# MaryLadder_8bits.net
KiCad netlist of a schematic drawn in Altium Designer
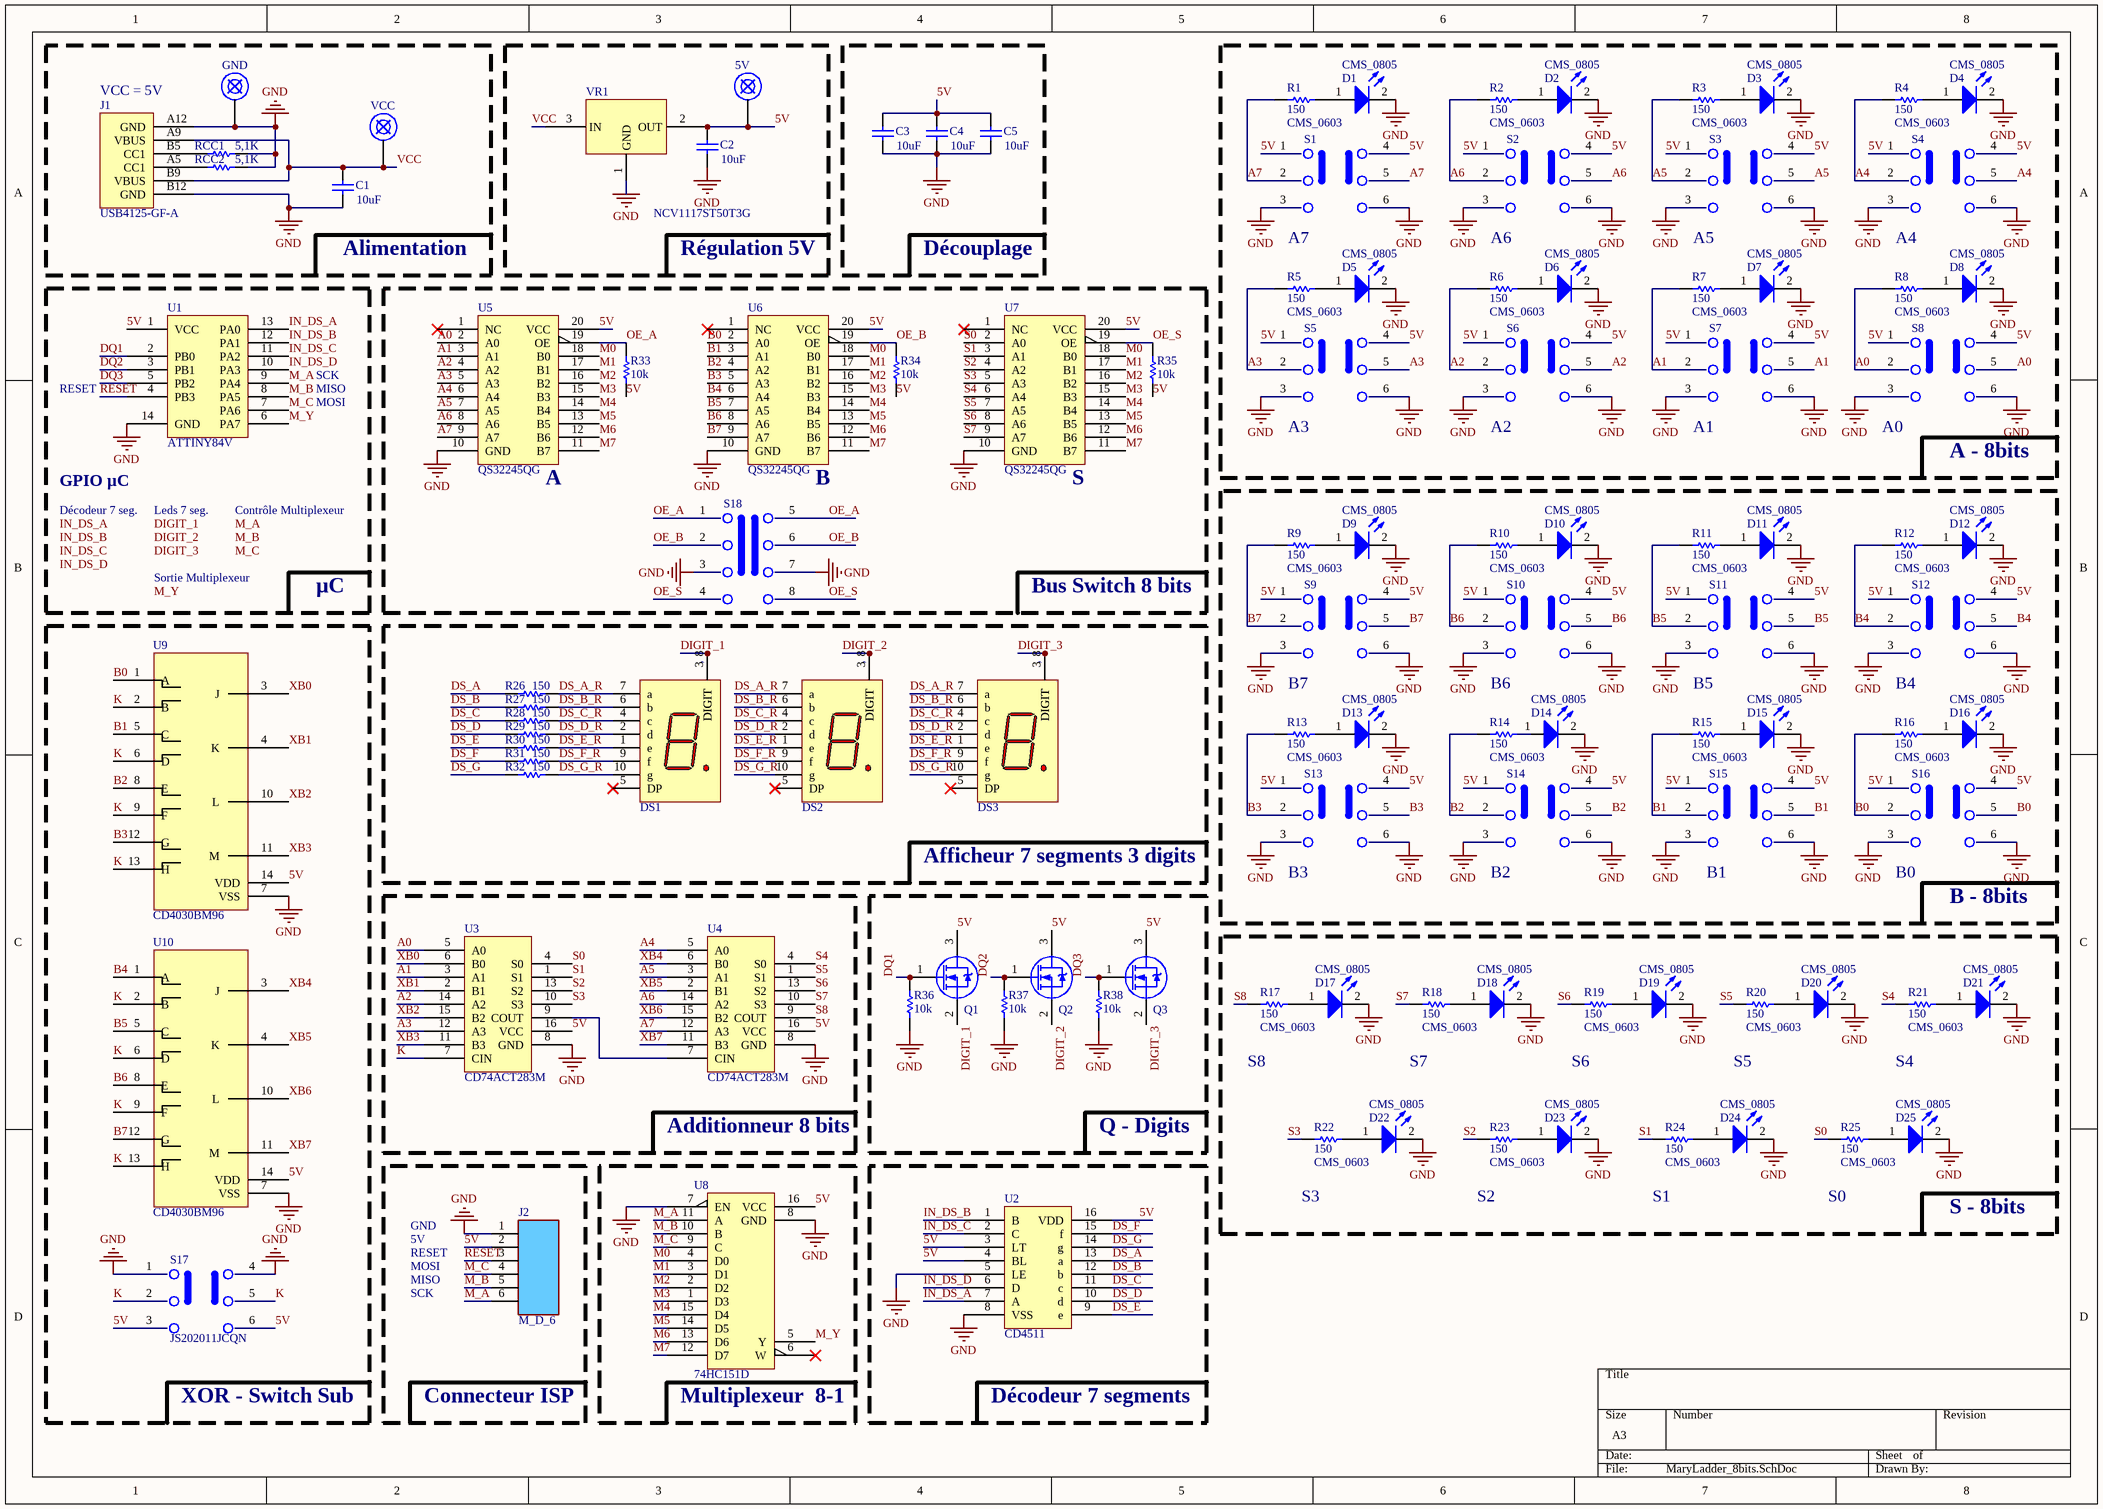
[diagram p0: MaryLadder_8bits.SchDoc]

(export (version "E")
  (design (tool "Eeschema 10.0.6"))
  (components
    (comp (ref "5V")
      (value "POINT_TEST_CMS_2MM")
      (footprint "POINT_TEST_CMS_2MM")
      (libsource (lib "MaryLab Projets") (part "POINT_TEST_CMS_2MM"))
    )
    (comp (ref "C1")
      (value "10uF")
      (footprint "CONDENSATEUR_CMS_0805")
      (description "CONDENSATEUR CMS CERAMIQUE 0805")
      (fields (field (name "Comment") "CMS_0805"))
      (libsource (lib "composants passifs") (part "CONDENSATEUR_CMS_CER_0805"))
    )
    (comp (ref "C2")
      (value "10uF")
      (footprint "CONDENSATEUR_CMS_0805")
      (description "CONDENSATEUR CMS CERAMIQUE 0805")
      (fields (field (name "Comment") "CMS_0805"))
      (libsource (lib "composants passifs") (part "CONDENSATEUR_CMS_CER_0805"))
    )
    (comp (ref "C3")
      (value "10uF")
      (footprint "CONDENSATEUR_CMS_0805")
      (description "CONDENSATEUR CMS CERAMIQUE 0805")
      (fields (field (name "Comment") "CMS_0805"))
      (libsource (lib "composants passifs") (part "CONDENSATEUR_CMS_CER_0805"))
    )
    (comp (ref "C4")
      (value "10uF")
      (footprint "CONDENSATEUR_CMS_0805")
      (description "CONDENSATEUR CMS CERAMIQUE 0805")
      (fields (field (name "Comment") "CMS_0805"))
      (libsource (lib "composants passifs") (part "CONDENSATEUR_CMS_CER_0805"))
    )
    (comp (ref "C5")
      (value "10uF")
      (footprint "CONDENSATEUR_CMS_0805")
      (description "CONDENSATEUR CMS CERAMIQUE 0805")
      (fields (field (name "Comment") "CMS_0805"))
      (libsource (lib "composants passifs") (part "CONDENSATEUR_CMS_CER_0805"))
    )
    (comp (ref "D1")
      (value "LED_CMS_0805")
      (footprint "LED_CMS_0805")
      (description "LED CMS 0805")
      (fields (field (name "TYPE") "CMS_0805"))
      (libsource (lib "affichage") (part "LED_CMS_0805"))
    )
    (comp (ref "D2")
      (value "LED_CMS_0805")
      (footprint "LED_CMS_0805")
      (description "LED CMS 0805")
      (fields (field (name "TYPE") "CMS_0805"))
      (libsource (lib "affichage") (part "LED_CMS_0805"))
    )
    (comp (ref "D3")
      (value "LED_CMS_0805")
      (footprint "LED_CMS_0805")
      (description "LED CMS 0805")
      (fields (field (name "TYPE") "CMS_0805"))
      (libsource (lib "affichage") (part "LED_CMS_0805"))
    )
    (comp (ref "D4")
      (value "LED_CMS_0805")
      (footprint "LED_CMS_0805")
      (description "LED CMS 0805")
      (fields (field (name "TYPE") "CMS_0805"))
      (libsource (lib "affichage") (part "LED_CMS_0805"))
    )
    (comp (ref "D5")
      (value "LED_CMS_0805")
      (footprint "LED_CMS_0805")
      (description "LED CMS 0805")
      (fields (field (name "TYPE") "CMS_0805"))
      (libsource (lib "affichage") (part "LED_CMS_0805"))
    )
    (comp (ref "D6")
      (value "LED_CMS_0805")
      (footprint "LED_CMS_0805")
      (description "LED CMS 0805")
      (fields (field (name "TYPE") "CMS_0805"))
      (libsource (lib "affichage") (part "LED_CMS_0805"))
    )
    (comp (ref "D7")
      (value "LED_CMS_0805")
      (footprint "LED_CMS_0805")
      (description "LED CMS 0805")
      (fields (field (name "TYPE") "CMS_0805"))
      (libsource (lib "affichage") (part "LED_CMS_0805"))
    )
    (comp (ref "D8")
      (value "LED_CMS_0805")
      (footprint "LED_CMS_0805")
      (description "LED CMS 0805")
      (fields (field (name "TYPE") "CMS_0805"))
      (libsource (lib "affichage") (part "LED_CMS_0805"))
    )
    (comp (ref "D9")
      (value "LED_CMS_0805")
      (footprint "LED_CMS_0805")
      (description "LED CMS 0805")
      (fields (field (name "TYPE") "CMS_0805"))
      (libsource (lib "affichage") (part "LED_CMS_0805"))
    )
    (comp (ref "D10")
      (value "LED_CMS_0805")
      (footprint "LED_CMS_0805")
      (description "LED CMS 0805")
      (fields (field (name "TYPE") "CMS_0805"))
      (libsource (lib "affichage") (part "LED_CMS_0805"))
    )
    (comp (ref "D11")
      (value "LED_CMS_0805")
      (footprint "LED_CMS_0805")
      (description "LED CMS 0805")
      (fields (field (name "TYPE") "CMS_0805"))
      (libsource (lib "affichage") (part "LED_CMS_0805"))
    )
    (comp (ref "D12")
      (value "LED_CMS_0805")
      (footprint "LED_CMS_0805")
      (description "LED CMS 0805")
      (fields (field (name "TYPE") "CMS_0805"))
      (libsource (lib "affichage") (part "LED_CMS_0805"))
    )
    (comp (ref "D13")
      (value "LED_CMS_0805")
      (footprint "LED_CMS_0805")
      (description "LED CMS 0805")
      (fields (field (name "TYPE") "CMS_0805"))
      (libsource (lib "affichage") (part "LED_CMS_0805"))
    )
    (comp (ref "D14")
      (value "LED_CMS_0805")
      (footprint "LED_CMS_0805")
      (description "LED CMS 0805")
      (fields (field (name "TYPE") "CMS_0805"))
      (libsource (lib "affichage") (part "LED_CMS_0805"))
    )
    (comp (ref "D15")
      (value "LED_CMS_0805")
      (footprint "LED_CMS_0805")
      (description "LED CMS 0805")
      (fields (field (name "TYPE") "CMS_0805"))
      (libsource (lib "affichage") (part "LED_CMS_0805"))
    )
    (comp (ref "D16")
      (value "LED_CMS_0805")
      (footprint "LED_CMS_0805")
      (description "LED CMS 0805")
      (fields (field (name "TYPE") "CMS_0805"))
      (libsource (lib "affichage") (part "LED_CMS_0805"))
    )
    (comp (ref "D17")
      (value "LED_CMS_0805")
      (footprint "LED_CMS_0805")
      (description "LED CMS 0805")
      (fields (field (name "TYPE") "CMS_0805"))
      (libsource (lib "affichage") (part "LED_CMS_0805"))
    )
    (comp (ref "D18")
      (value "LED_CMS_0805")
      (footprint "LED_CMS_0805")
      (description "LED CMS 0805")
      (fields (field (name "TYPE") "CMS_0805"))
      (libsource (lib "affichage") (part "LED_CMS_0805"))
    )
    (comp (ref "D19")
      (value "LED_CMS_0805")
      (footprint "LED_CMS_0805")
      (description "LED CMS 0805")
      (fields (field (name "TYPE") "CMS_0805"))
      (libsource (lib "affichage") (part "LED_CMS_0805"))
    )
    (comp (ref "D20")
      (value "LED_CMS_0805")
      (footprint "LED_CMS_0805")
      (description "LED CMS 0805")
      (fields (field (name "TYPE") "CMS_0805"))
      (libsource (lib "affichage") (part "LED_CMS_0805"))
    )
    (comp (ref "D21")
      (value "LED_CMS_0805")
      (footprint "LED_CMS_0805")
      (description "LED CMS 0805")
      (fields (field (name "TYPE") "CMS_0805"))
      (libsource (lib "affichage") (part "LED_CMS_0805"))
    )
    (comp (ref "D22")
      (value "LED_CMS_0805")
      (footprint "LED_CMS_0805")
      (description "LED CMS 0805")
      (fields (field (name "TYPE") "CMS_0805"))
      (libsource (lib "affichage") (part "LED_CMS_0805"))
    )
    (comp (ref "D23")
      (value "LED_CMS_0805")
      (footprint "LED_CMS_0805")
      (description "LED CMS 0805")
      (fields (field (name "TYPE") "CMS_0805"))
      (libsource (lib "affichage") (part "LED_CMS_0805"))
    )
    (comp (ref "D24")
      (value "LED_CMS_0805")
      (footprint "LED_CMS_0805")
      (description "LED CMS 0805")
      (fields (field (name "TYPE") "CMS_0805"))
      (libsource (lib "affichage") (part "LED_CMS_0805"))
    )
    (comp (ref "D25")
      (value "LED_CMS_0805")
      (footprint "LED_CMS_0805")
      (description "LED CMS 0805")
      (fields (field (name "TYPE") "CMS_0805"))
      (libsource (lib "affichage") (part "LED_CMS_0805"))
    )
    (comp (ref "DS1")
      (value "AFFICHEUR_7_SEGM_A.C_1_DIGIT")
      (footprint "AFFICHEUR_7_SEGM_A.C_1_DIGIT")
      (description "VDMR10A1 - DISPLAY 7SEG 0.39\" SGL RED 10SMD")
      (libsource (lib "MaryLab Projets") (part "AFFICHEUR_7_SEGM_A.C_1_DIGIT"))
    )
    (comp (ref "DS2")
      (value "AFFICHEUR_7_SEGM_A.C_1_DIGIT")
      (footprint "AFFICHEUR_7_SEGM_A.C_1_DIGIT")
      (description "VDMR10A1 - DISPLAY 7SEG 0.39\" SGL RED 10SMD")
      (libsource (lib "MaryLab Projets") (part "AFFICHEUR_7_SEGM_A.C_1_DIGIT"))
    )
    (comp (ref "DS3")
      (value "AFFICHEUR_7_SEGM_A.C_1_DIGIT")
      (footprint "AFFICHEUR_7_SEGM_A.C_1_DIGIT")
      (description "VDMR10A1 - DISPLAY 7SEG 0.39\" SGL RED 10SMD")
      (libsource (lib "MaryLab Projets") (part "AFFICHEUR_7_SEGM_A.C_1_DIGIT"))
    )
    (comp (ref "GND")
      (value "POINT_TEST_CMS_2MM")
      (footprint "POINT_TEST_CMS_2MM")
      (libsource (lib "MaryLab Projets") (part "POINT_TEST_CMS_2MM"))
    )
    (comp (ref "J1")
      (value "USB4125-GF-A")
      (footprint "TYPE-C FEMELLE")
      (description "CONN RCPT TYPE C 6P SMD RA")
      (libsource (lib "MaryLab Projets") (part "TYPE-C FEMELLE"))
    )
    (comp (ref "J2")
      (value "BARRETTE_6 CONTACTS_1 RANGEE_MALE_DROITE")
      (footprint "BARRETTE_6_M_D")
      (description "BARRETTE 6 CONTACTS 1 RANGEE MALE DROITE")
      (fields (field (name "TYPE") "M_D_6"))
      (libsource (lib "connecteurs") (part "BARRETTE_6 CONTACTS_1 RANGEE_MALE_DROITE"))
    )
    (comp (ref "Q1")
      (value "TRANSISTOR_MOSFET-N_SOT23_GSD")
      (footprint "TRANSISTOR_MOSFET-N_SOT23_GSD")
      (description "TRANSISTOR MOSFET CANAL N BOITIER SOT23_GSD")
      (libsource (lib "composants actifs") (part "TRANSISTOR_MOSFET-N_SOT23_GSD"))
    )
    (comp (ref "Q2")
      (value "TRANSISTOR_MOSFET-N_SOT23_GSD")
      (footprint "TRANSISTOR_MOSFET-N_SOT23_GSD")
      (description "TRANSISTOR MOSFET CANAL N BOITIER SOT23_GSD")
      (libsource (lib "composants actifs") (part "TRANSISTOR_MOSFET-N_SOT23_GSD"))
    )
    (comp (ref "Q3")
      (value "TRANSISTOR_MOSFET-N_SOT23_GSD")
      (footprint "TRANSISTOR_MOSFET-N_SOT23_GSD")
      (description "TRANSISTOR MOSFET CANAL N BOITIER SOT23_GSD")
      (libsource (lib "composants actifs") (part "TRANSISTOR_MOSFET-N_SOT23_GSD"))
    )
    (comp (ref "R1")
      (value "150")
      (footprint "RESISTANCE_CMS_0603")
      (description "RESISTANCE CMS 0603")
      (fields (field (name "TYPE") "CMS_0603") (field (name "Comment") "RESISTANCE_CMS_0603"))
      (libsource (lib "composants passifs") (part "RESISTANCE_CMS_0603"))
    )
    (comp (ref "R2")
      (value "150")
      (footprint "RESISTANCE_CMS_0603")
      (description "RESISTANCE CMS 0603")
      (fields (field (name "TYPE") "CMS_0603") (field (name "Comment") "RESISTANCE_CMS_0603"))
      (libsource (lib "composants passifs") (part "RESISTANCE_CMS_0603"))
    )
    (comp (ref "R3")
      (value "150")
      (footprint "RESISTANCE_CMS_0603")
      (description "RESISTANCE CMS 0603")
      (fields (field (name "TYPE") "CMS_0603") (field (name "Comment") "RESISTANCE_CMS_0603"))
      (libsource (lib "composants passifs") (part "RESISTANCE_CMS_0603"))
    )
    (comp (ref "R4")
      (value "150")
      (footprint "RESISTANCE_CMS_0603")
      (description "RESISTANCE CMS 0603")
      (fields (field (name "TYPE") "CMS_0603") (field (name "Comment") "RESISTANCE_CMS_0603"))
      (libsource (lib "composants passifs") (part "RESISTANCE_CMS_0603"))
    )
    (comp (ref "R5")
      (value "150")
      (footprint "RESISTANCE_CMS_0603")
      (description "RESISTANCE CMS 0603")
      (fields (field (name "TYPE") "CMS_0603") (field (name "Comment") "RESISTANCE_CMS_0603"))
      (libsource (lib "composants passifs") (part "RESISTANCE_CMS_0603"))
    )
    (comp (ref "R6")
      (value "150")
      (footprint "RESISTANCE_CMS_0603")
      (description "RESISTANCE CMS 0603")
      (fields (field (name "TYPE") "CMS_0603") (field (name "Comment") "RESISTANCE_CMS_0603"))
      (libsource (lib "composants passifs") (part "RESISTANCE_CMS_0603"))
    )
    (comp (ref "R7")
      (value "150")
      (footprint "RESISTANCE_CMS_0603")
      (description "RESISTANCE CMS 0603")
      (fields (field (name "TYPE") "CMS_0603") (field (name "Comment") "RESISTANCE_CMS_0603"))
      (libsource (lib "composants passifs") (part "RESISTANCE_CMS_0603"))
    )
    (comp (ref "R8")
      (value "150")
      (footprint "RESISTANCE_CMS_0603")
      (description "RESISTANCE CMS 0603")
      (fields (field (name "TYPE") "CMS_0603") (field (name "Comment") "RESISTANCE_CMS_0603"))
      (libsource (lib "composants passifs") (part "RESISTANCE_CMS_0603"))
    )
    (comp (ref "R9")
      (value "150")
      (footprint "RESISTANCE_CMS_0603")
      (description "RESISTANCE CMS 0603")
      (fields (field (name "TYPE") "CMS_0603") (field (name "Comment") "RESISTANCE_CMS_0603"))
      (libsource (lib "composants passifs") (part "RESISTANCE_CMS_0603"))
    )
    (comp (ref "R10")
      (value "150")
      (footprint "RESISTANCE_CMS_0603")
      (description "RESISTANCE CMS 0603")
      (fields (field (name "TYPE") "CMS_0603") (field (name "Comment") "RESISTANCE_CMS_0603"))
      (libsource (lib "composants passifs") (part "RESISTANCE_CMS_0603"))
    )
    (comp (ref "R11")
      (value "150")
      (footprint "RESISTANCE_CMS_0603")
      (description "RESISTANCE CMS 0603")
      (fields (field (name "TYPE") "CMS_0603") (field (name "Comment") "RESISTANCE_CMS_0603"))
      (libsource (lib "composants passifs") (part "RESISTANCE_CMS_0603"))
    )
    (comp (ref "R12")
      (value "150")
      (footprint "RESISTANCE_CMS_0603")
      (description "RESISTANCE CMS 0603")
      (fields (field (name "TYPE") "CMS_0603") (field (name "Comment") "RESISTANCE_CMS_0603"))
      (libsource (lib "composants passifs") (part "RESISTANCE_CMS_0603"))
    )
    (comp (ref "R13")
      (value "150")
      (footprint "RESISTANCE_CMS_0603")
      (description "RESISTANCE CMS 0603")
      (fields (field (name "TYPE") "CMS_0603") (field (name "Comment") "RESISTANCE_CMS_0603"))
      (libsource (lib "composants passifs") (part "RESISTANCE_CMS_0603"))
    )
    (comp (ref "R14")
      (value "150")
      (footprint "RESISTANCE_CMS_0603")
      (description "RESISTANCE CMS 0603")
      (fields (field (name "TYPE") "CMS_0603") (field (name "Comment") "RESISTANCE_CMS_0603"))
      (libsource (lib "composants passifs") (part "RESISTANCE_CMS_0603"))
    )
    (comp (ref "R15")
      (value "150")
      (footprint "RESISTANCE_CMS_0603")
      (description "RESISTANCE CMS 0603")
      (fields (field (name "TYPE") "CMS_0603") (field (name "Comment") "RESISTANCE_CMS_0603"))
      (libsource (lib "composants passifs") (part "RESISTANCE_CMS_0603"))
    )
    (comp (ref "R16")
      (value "150")
      (footprint "RESISTANCE_CMS_0603")
      (description "RESISTANCE CMS 0603")
      (fields (field (name "TYPE") "CMS_0603") (field (name "Comment") "RESISTANCE_CMS_0603"))
      (libsource (lib "composants passifs") (part "RESISTANCE_CMS_0603"))
    )
    (comp (ref "R17")
      (value "150")
      (footprint "RESISTANCE_CMS_0603")
      (description "RESISTANCE CMS 0603")
      (fields (field (name "TYPE") "CMS_0603") (field (name "Comment") "RESISTANCE_CMS_0603"))
      (libsource (lib "composants passifs") (part "RESISTANCE_CMS_0603"))
    )
    (comp (ref "R18")
      (value "150")
      (footprint "RESISTANCE_CMS_0603")
      (description "RESISTANCE CMS 0603")
      (fields (field (name "TYPE") "CMS_0603") (field (name "Comment") "RESISTANCE_CMS_0603"))
      (libsource (lib "composants passifs") (part "RESISTANCE_CMS_0603"))
    )
    (comp (ref "R19")
      (value "150")
      (footprint "RESISTANCE_CMS_0603")
      (description "RESISTANCE CMS 0603")
      (fields (field (name "TYPE") "CMS_0603") (field (name "Comment") "RESISTANCE_CMS_0603"))
      (libsource (lib "composants passifs") (part "RESISTANCE_CMS_0603"))
    )
    (comp (ref "R20")
      (value "150")
      (footprint "RESISTANCE_CMS_0603")
      (description "RESISTANCE CMS 0603")
      (fields (field (name "TYPE") "CMS_0603") (field (name "Comment") "RESISTANCE_CMS_0603"))
      (libsource (lib "composants passifs") (part "RESISTANCE_CMS_0603"))
    )
    (comp (ref "R21")
      (value "150")
      (footprint "RESISTANCE_CMS_0603")
      (description "RESISTANCE CMS 0603")
      (fields (field (name "TYPE") "CMS_0603") (field (name "Comment") "RESISTANCE_CMS_0603"))
      (libsource (lib "composants passifs") (part "RESISTANCE_CMS_0603"))
    )
    (comp (ref "R22")
      (value "150")
      (footprint "RESISTANCE_CMS_0603")
      (description "RESISTANCE CMS 0603")
      (fields (field (name "TYPE") "CMS_0603") (field (name "Comment") "RESISTANCE_CMS_0603"))
      (libsource (lib "composants passifs") (part "RESISTANCE_CMS_0603"))
    )
    (comp (ref "R23")
      (value "150")
      (footprint "RESISTANCE_CMS_0603")
      (description "RESISTANCE CMS 0603")
      (fields (field (name "TYPE") "CMS_0603") (field (name "Comment") "RESISTANCE_CMS_0603"))
      (libsource (lib "composants passifs") (part "RESISTANCE_CMS_0603"))
    )
    (comp (ref "R24")
      (value "150")
      (footprint "RESISTANCE_CMS_0603")
      (description "RESISTANCE CMS 0603")
      (fields (field (name "TYPE") "CMS_0603") (field (name "Comment") "RESISTANCE_CMS_0603"))
      (libsource (lib "composants passifs") (part "RESISTANCE_CMS_0603"))
    )
    (comp (ref "R25")
      (value "150")
      (footprint "RESISTANCE_CMS_0603")
      (description "RESISTANCE CMS 0603")
      (fields (field (name "TYPE") "CMS_0603") (field (name "Comment") "RESISTANCE_CMS_0603"))
      (libsource (lib "composants passifs") (part "RESISTANCE_CMS_0603"))
    )
    (comp (ref "R26")
      (value "150")
      (footprint "RESISTANCE_CMS_0603")
      (description "RESISTANCE CMS 0603")
      (fields (field (name "Comment") "RESISTANCE_CMS_0603"))
      (libsource (lib "composants passifs") (part "RESISTANCE_CMS_0603"))
    )
    (comp (ref "R27")
      (value "150")
      (footprint "RESISTANCE_CMS_0603")
      (description "RESISTANCE CMS 0603")
      (fields (field (name "Comment") "RESISTANCE_CMS_0603"))
      (libsource (lib "composants passifs") (part "RESISTANCE_CMS_0603"))
    )
    (comp (ref "R28")
      (value "150")
      (footprint "RESISTANCE_CMS_0603")
      (description "RESISTANCE CMS 0603")
      (fields (field (name "Comment") "RESISTANCE_CMS_0603"))
      (libsource (lib "composants passifs") (part "RESISTANCE_CMS_0603"))
    )
    (comp (ref "R29")
      (value "150")
      (footprint "RESISTANCE_CMS_0603")
      (description "RESISTANCE CMS 0603")
      (fields (field (name "Comment") "RESISTANCE_CMS_0603"))
      (libsource (lib "composants passifs") (part "RESISTANCE_CMS_0603"))
    )
    (comp (ref "R30")
      (value "150")
      (footprint "RESISTANCE_CMS_0603")
      (description "RESISTANCE CMS 0603")
      (fields (field (name "Comment") "RESISTANCE_CMS_0603"))
      (libsource (lib "composants passifs") (part "RESISTANCE_CMS_0603"))
    )
    (comp (ref "R31")
      (value "150")
      (footprint "RESISTANCE_CMS_0603")
      (description "RESISTANCE CMS 0603")
      (fields (field (name "Comment") "RESISTANCE_CMS_0603"))
      (libsource (lib "composants passifs") (part "RESISTANCE_CMS_0603"))
    )
    (comp (ref "R32")
      (value "150")
      (footprint "RESISTANCE_CMS_0603")
      (description "RESISTANCE CMS 0603")
      (fields (field (name "Comment") "RESISTANCE_CMS_0603"))
      (libsource (lib "composants passifs") (part "RESISTANCE_CMS_0603"))
    )
    (comp (ref "R33")
      (value "10k")
      (footprint "RESISTANCE_CMS_0603")
      (description "RESISTANCE CMS 0603")
      (fields (field (name "Comment") "RESISTANCE_CMS_0603"))
      (libsource (lib "composants passifs") (part "RESISTANCE_CMS_0603"))
    )
    (comp (ref "R34")
      (value "10k")
      (footprint "RESISTANCE_CMS_0603")
      (description "RESISTANCE CMS 0603")
      (fields (field (name "Comment") "RESISTANCE_CMS_0603"))
      (libsource (lib "composants passifs") (part "RESISTANCE_CMS_0603"))
    )
    (comp (ref "R35")
      (value "10k")
      (footprint "RESISTANCE_CMS_0603")
      (description "RESISTANCE CMS 0603")
      (fields (field (name "Comment") "RESISTANCE_CMS_0603"))
      (libsource (lib "composants passifs") (part "RESISTANCE_CMS_0603"))
    )
    (comp (ref "R36")
      (value "10k")
      (footprint "RESISTANCE_CMS_0603")
      (description "RESISTANCE CMS 0603")
      (fields (field (name "Comment") "RESISTANCE_CMS_0603"))
      (libsource (lib "composants passifs") (part "RESISTANCE_CMS_0603"))
    )
    (comp (ref "R37")
      (value "10k")
      (footprint "RESISTANCE_CMS_0603")
      (description "RESISTANCE CMS 0603")
      (fields (field (name "Comment") "RESISTANCE_CMS_0603"))
      (libsource (lib "composants passifs") (part "RESISTANCE_CMS_0603"))
    )
    (comp (ref "R38")
      (value "10k")
      (footprint "RESISTANCE_CMS_0603")
      (description "RESISTANCE CMS 0603")
      (fields (field (name "Comment") "RESISTANCE_CMS_0603"))
      (libsource (lib "composants passifs") (part "RESISTANCE_CMS_0603"))
    )
    (comp (ref "RCC1")
      (value "5,1K")
      (footprint "RESISTANCE_CMS_0603")
      (description "RESISTANCE CMS 0603")
      (fields (field (name "Comment") "RESISTANCE_CMS_0603"))
      (libsource (lib "composants passifs") (part "RESISTANCE_CMS_0603"))
    )
    (comp (ref "RCC2")
      (value "5,1K")
      (footprint "RESISTANCE_CMS_0603")
      (description "RESISTANCE CMS 0603")
      (fields (field (name "Comment") "RESISTANCE_CMS_0603"))
      (libsource (lib "composants passifs") (part "RESISTANCE_CMS_0603"))
    )
    (comp (ref "S1")
      (value "JS202011JCQN")
      (footprint "JS202011JCQN")
      (description "SWITCH SLIDE DPDT 300MA 6V")
      (libsource (lib "MaryLab Projets") (part "JS202011JCQN"))
    )
    (comp (ref "S2")
      (value "JS202011JCQN")
      (footprint "JS202011JCQN")
      (description "SWITCH SLIDE DPDT 300MA 6V")
      (libsource (lib "MaryLab Projets") (part "JS202011JCQN"))
    )
    (comp (ref "S3")
      (value "JS202011JCQN")
      (footprint "JS202011JCQN")
      (description "SWITCH SLIDE DPDT 300MA 6V")
      (libsource (lib "MaryLab Projets") (part "JS202011JCQN"))
    )
    (comp (ref "S4")
      (value "JS202011JCQN")
      (footprint "JS202011JCQN")
      (description "SWITCH SLIDE DPDT 300MA 6V")
      (libsource (lib "MaryLab Projets") (part "JS202011JCQN"))
    )
    (comp (ref "S5")
      (value "JS202011JCQN")
      (footprint "JS202011JCQN")
      (description "SWITCH SLIDE DPDT 300MA 6V")
      (libsource (lib "MaryLab Projets") (part "JS202011JCQN"))
    )
    (comp (ref "S6")
      (value "JS202011JCQN")
      (footprint "JS202011JCQN")
      (description "SWITCH SLIDE DPDT 300MA 6V")
      (libsource (lib "MaryLab Projets") (part "JS202011JCQN"))
    )
    (comp (ref "S7")
      (value "JS202011JCQN")
      (footprint "JS202011JCQN")
      (description "SWITCH SLIDE DPDT 300MA 6V")
      (libsource (lib "MaryLab Projets") (part "JS202011JCQN"))
    )
    (comp (ref "S8")
      (value "JS202011JCQN")
      (footprint "JS202011JCQN")
      (description "SWITCH SLIDE DPDT 300MA 6V")
      (libsource (lib "MaryLab Projets") (part "JS202011JCQN"))
    )
    (comp (ref "S9")
      (value "JS202011JCQN")
      (footprint "JS202011JCQN")
      (description "SWITCH SLIDE DPDT 300MA 6V")
      (libsource (lib "MaryLab Projets") (part "JS202011JCQN"))
    )
    (comp (ref "S10")
      (value "JS202011JCQN")
      (footprint "JS202011JCQN")
      (description "SWITCH SLIDE DPDT 300MA 6V")
      (libsource (lib "MaryLab Projets") (part "JS202011JCQN"))
    )
    (comp (ref "S11")
      (value "JS202011JCQN")
      (footprint "JS202011JCQN")
      (description "SWITCH SLIDE DPDT 300MA 6V")
      (libsource (lib "MaryLab Projets") (part "JS202011JCQN"))
    )
    (comp (ref "S12")
      (value "JS202011JCQN")
      (footprint "JS202011JCQN")
      (description "SWITCH SLIDE DPDT 300MA 6V")
      (libsource (lib "MaryLab Projets") (part "JS202011JCQN"))
    )
    (comp (ref "S13")
      (value "JS202011JCQN")
      (footprint "JS202011JCQN")
      (description "SWITCH SLIDE DPDT 300MA 6V")
      (libsource (lib "MaryLab Projets") (part "JS202011JCQN"))
    )
    (comp (ref "S14")
      (value "JS202011JCQN")
      (footprint "JS202011JCQN")
      (description "SWITCH SLIDE DPDT 300MA 6V")
      (libsource (lib "MaryLab Projets") (part "JS202011JCQN"))
    )
    (comp (ref "S15")
      (value "JS202011JCQN")
      (footprint "JS202011JCQN")
      (description "SWITCH SLIDE DPDT 300MA 6V")
      (libsource (lib "MaryLab Projets") (part "JS202011JCQN"))
    )
    (comp (ref "S16")
      (value "JS202011JCQN")
      (footprint "JS202011JCQN")
      (description "SWITCH SLIDE DPDT 300MA 6V")
      (libsource (lib "MaryLab Projets") (part "JS202011JCQN"))
    )
    (comp (ref "S17")
      (value "JS202011JCQN")
      (footprint "JS202011JCQN")
      (description "SWITCH SLIDE DPDT 300MA 6V")
      (libsource (lib "MaryLab Projets") (part "JS202011JCQN"))
    )
    (comp (ref "S18")
      (value "JS203011JCQN")
      (footprint "JS203011JCQN")
      (description "SWITCH SLIDE DP3T 300MA 6V")
      (libsource (lib "MaryLab Projets") (part "JS203011JCQN"))
    )
    (comp (ref "U1")
      (value "ATTINY84V")
      (footprint "ATTINY84V-10SSU")
      (description "AVR series Microcontrôleurs IC 8 bits 10MHz 8Ko (4K x 16) FLASH 14-SOIC")
      (libsource (lib "MaryLab Projets") (part "ATTINY84V-10SSU"))
    )
    (comp (ref "U2")
      (value "CD4511")
      (footprint "CD4511")
      (description "CMOS BCD to 7 Segment Latch Decoder Drivers")
      (libsource (lib "MaryLab Projets") (part "CD4511"))
    )
    (comp (ref "U3")
      (value "CD74ACT283M")
      (footprint "CD74ACT283M")
      (description "4-Bit Binary Fill Adder With Fast Carry")
      (libsource (lib "MaryLab Projets") (part "CD74ACT283M"))
    )
    (comp (ref "U4")
      (value "CD74ACT283M")
      (footprint "CD74ACT283M")
      (description "4-Bit Binary Fill Adder With Fast Carry")
      (libsource (lib "MaryLab Projets") (part "CD74ACT283M"))
    )
    (comp (ref "U5")
      (value "QS32245QG")
      (footprint "QS32245QG")
      (description "IC BUS SWITCH 1 X 8:1 20QSOP")
      (libsource (lib "MaryLab Projets") (part "QS32245QG"))
    )
    (comp (ref "U6")
      (value "QS32245QG")
      (footprint "QS32245QG")
      (description "IC BUS SWITCH 1 X 8:1 20QSOP")
      (libsource (lib "MaryLab Projets") (part "QS32245QG"))
    )
    (comp (ref "U7")
      (value "QS32245QG")
      (footprint "QS32245QG")
      (description "IC BUS SWITCH 1 X 8:1 20QSOP")
      (libsource (lib "MaryLab Projets") (part "QS32245QG"))
    )
    (comp (ref "U8")
      (value "74HC151D")
      (footprint "74HC151D")
      (description "IC MULTIPLEXER 1 X 8:1")
      (libsource (lib "MaryLab Projets") (part "74HC151D"))
    )
    (comp (ref "U9")
      (value "CD4030BM96")
      (footprint "CD4030BM96")
      (description "IC GATE XOR 4CH 2-INP 14SOIC")
      (libsource (lib "MaryLab Projets") (part "CD4030BM96"))
    )
    (comp (ref "U10")
      (value "CD4030BM96")
      (footprint "CD4030BM96")
      (description "IC GATE XOR 4CH 2-INP 14SOIC")
      (libsource (lib "MaryLab Projets") (part "CD4030BM96"))
    )
    (comp (ref "VCC")
      (value "POINT_TEST_CMS_2MM")
      (footprint "POINT_TEST_CMS_2MM")
      (libsource (lib "MaryLab Projets") (part "POINT_TEST_CMS_2MM"))
    )
    (comp (ref "VR1")
      (value "NCV1117ST50T3G")
      (footprint "NCV1117ST50T3G")
      (description "IC REG LINEAR 5V 1A SOT223")
      (libsource (lib "MaryLab Projets") (part "NCV1117ST50T3G"))
    )
  )
  (nets
    (net (code "1") (name "/5V") (class "Default")
      (node (ref "5V") (pin "1") (pinfunction "1_1") (pintype "passive"))
      (node (ref "C2") (pin "2") (pinfunction "2_2") (pintype "passive"))
      (node (ref "C3") (pin "2") (pinfunction "2_2") (pintype "passive"))
      (node (ref "C4") (pin "2") (pinfunction "2_2") (pintype "passive"))
      (node (ref "C5") (pin "2") (pinfunction "2_2") (pintype "passive"))
      (node (ref "J2") (pin "2") (pinfunction "2_2") (pintype "passive"))
      (node (ref "Q1") (pin "3") (pinfunction "D_3") (pintype "passive"))
      (node (ref "Q2") (pin "3") (pinfunction "D_3") (pintype "passive"))
      (node (ref "Q3") (pin "3") (pinfunction "D_3") (pintype "passive"))
      (node (ref "R33") (pin "1") (pinfunction "1_1") (pintype "passive"))
      (node (ref "R34") (pin "1") (pinfunction "1_1") (pintype "passive"))
      (node (ref "R35") (pin "1") (pinfunction "1_1") (pintype "passive"))
      (node (ref "S1") (pin "1") (pinfunction "1_1") (pintype "passive"))
      (node (ref "S1") (pin "4") (pinfunction "4_4") (pintype "passive"))
      (node (ref "S10") (pin "1") (pinfunction "1_1") (pintype "passive"))
      (node (ref "S10") (pin "4") (pinfunction "4_4") (pintype "passive"))
      (node (ref "S11") (pin "1") (pinfunction "1_1") (pintype "passive"))
      (node (ref "S11") (pin "4") (pinfunction "4_4") (pintype "passive"))
      (node (ref "S12") (pin "1") (pinfunction "1_1") (pintype "passive"))
      (node (ref "S12") (pin "4") (pinfunction "4_4") (pintype "passive"))
      (node (ref "S13") (pin "1") (pinfunction "1_1") (pintype "passive"))
      (node (ref "S13") (pin "4") (pinfunction "4_4") (pintype "passive"))
      (node (ref "S14") (pin "1") (pinfunction "1_1") (pintype "passive"))
      (node (ref "S14") (pin "4") (pinfunction "4_4") (pintype "passive"))
      (node (ref "S15") (pin "1") (pinfunction "1_1") (pintype "passive"))
      (node (ref "S15") (pin "4") (pinfunction "4_4") (pintype "passive"))
      (node (ref "S16") (pin "1") (pinfunction "1_1") (pintype "passive"))
      (node (ref "S16") (pin "4") (pinfunction "4_4") (pintype "passive"))
      (node (ref "S17") (pin "3") (pinfunction "3_3") (pintype "passive"))
      (node (ref "S17") (pin "6") (pinfunction "6_6") (pintype "passive"))
      (node (ref "S2") (pin "1") (pinfunction "1_1") (pintype "passive"))
      (node (ref "S2") (pin "4") (pinfunction "4_4") (pintype "passive"))
      (node (ref "S3") (pin "1") (pinfunction "1_1") (pintype "passive"))
      (node (ref "S3") (pin "4") (pinfunction "4_4") (pintype "passive"))
      (node (ref "S4") (pin "1") (pinfunction "1_1") (pintype "passive"))
      (node (ref "S4") (pin "4") (pinfunction "4_4") (pintype "passive"))
      (node (ref "S5") (pin "1") (pinfunction "1_1") (pintype "passive"))
      (node (ref "S5") (pin "4") (pinfunction "4_4") (pintype "passive"))
      (node (ref "S6") (pin "1") (pinfunction "1_1") (pintype "passive"))
      (node (ref "S6") (pin "4") (pinfunction "4_4") (pintype "passive"))
      (node (ref "S7") (pin "1") (pinfunction "1_1") (pintype "passive"))
      (node (ref "S7") (pin "4") (pinfunction "4_4") (pintype "passive"))
      (node (ref "S8") (pin "1") (pinfunction "1_1") (pintype "passive"))
      (node (ref "S8") (pin "4") (pinfunction "4_4") (pintype "passive"))
      (node (ref "S9") (pin "1") (pinfunction "1_1") (pintype "passive"))
      (node (ref "S9") (pin "4") (pinfunction "4_4") (pintype "passive"))
      (node (ref "U1") (pin "1") (pinfunction "VCC_1") (pintype "passive"))
      (node (ref "U10") (pin "14") (pinfunction "VDD_14") (pintype "passive"))
      (node (ref "U2") (pin "16") (pinfunction "VDD_16") (pintype "passive"))
      (node (ref "U2") (pin "3") (pinfunction "LT_3") (pintype "passive"))
      (node (ref "U2") (pin "4") (pinfunction "BL_4") (pintype "passive"))
      (node (ref "U3") (pin "16") (pinfunction "VCC_16") (pintype "passive"))
      (node (ref "U4") (pin "16") (pinfunction "VCC_16") (pintype "passive"))
      (node (ref "U5") (pin "20") (pinfunction "VCC_20") (pintype "passive"))
      (node (ref "U6") (pin "20") (pinfunction "VCC_20") (pintype "passive"))
      (node (ref "U7") (pin "20") (pinfunction "VCC_20") (pintype "passive"))
      (node (ref "U8") (pin "16") (pinfunction "VCC_16") (pintype "passive"))
      (node (ref "U9") (pin "14") (pinfunction "VDD_14") (pintype "passive"))
      (node (ref "VR1") (pin "2") (pinfunction "OUT_2") (pintype "passive"))
    )
    (net (code "2") (name "/A0") (class "Default")
      (node (ref "R8") (pin "1") (pinfunction "1_1") (pintype "passive"))
      (node (ref "S8") (pin "2") (pinfunction "2_2") (pintype "passive"))
      (node (ref "S8") (pin "5") (pinfunction "5_5") (pintype "passive"))
      (node (ref "U3") (pin "5") (pinfunction "A0_5") (pintype "passive"))
      (node (ref "U5") (pin "2") (pinfunction "A0_2") (pintype "passive"))
    )
    (net (code "3") (name "/A1") (class "Default")
      (node (ref "R7") (pin "1") (pinfunction "1_1") (pintype "passive"))
      (node (ref "S7") (pin "2") (pinfunction "2_2") (pintype "passive"))
      (node (ref "S7") (pin "5") (pinfunction "5_5") (pintype "passive"))
      (node (ref "U3") (pin "3") (pinfunction "A1_3") (pintype "passive"))
      (node (ref "U5") (pin "3") (pinfunction "A1_3") (pintype "passive"))
    )
    (net (code "4") (name "/A2") (class "Default")
      (node (ref "R6") (pin "1") (pinfunction "1_1") (pintype "passive"))
      (node (ref "S6") (pin "2") (pinfunction "2_2") (pintype "passive"))
      (node (ref "S6") (pin "5") (pinfunction "5_5") (pintype "passive"))
      (node (ref "U3") (pin "14") (pinfunction "A2_14") (pintype "passive"))
      (node (ref "U5") (pin "4") (pinfunction "A2_4") (pintype "passive"))
    )
    (net (code "5") (name "/A3") (class "Default")
      (node (ref "R5") (pin "1") (pinfunction "1_1") (pintype "passive"))
      (node (ref "S5") (pin "2") (pinfunction "2_2") (pintype "passive"))
      (node (ref "S5") (pin "5") (pinfunction "5_5") (pintype "passive"))
      (node (ref "U3") (pin "12") (pinfunction "A3_12") (pintype "passive"))
      (node (ref "U5") (pin "5") (pinfunction "A3_5") (pintype "passive"))
    )
    (net (code "6") (name "/A4") (class "Default")
      (node (ref "R4") (pin "1") (pinfunction "1_1") (pintype "passive"))
      (node (ref "S4") (pin "2") (pinfunction "2_2") (pintype "passive"))
      (node (ref "S4") (pin "5") (pinfunction "5_5") (pintype "passive"))
      (node (ref "U4") (pin "5") (pinfunction "A0_5") (pintype "passive"))
      (node (ref "U5") (pin "6") (pinfunction "A4_6") (pintype "passive"))
    )
    (net (code "7") (name "/A5") (class "Default")
      (node (ref "R3") (pin "1") (pinfunction "1_1") (pintype "passive"))
      (node (ref "S3") (pin "2") (pinfunction "2_2") (pintype "passive"))
      (node (ref "S3") (pin "5") (pinfunction "5_5") (pintype "passive"))
      (node (ref "U4") (pin "3") (pinfunction "A1_3") (pintype "passive"))
      (node (ref "U5") (pin "7") (pinfunction "A5_7") (pintype "passive"))
    )
    (net (code "8") (name "/A6") (class "Default")
      (node (ref "R2") (pin "1") (pinfunction "1_1") (pintype "passive"))
      (node (ref "S2") (pin "2") (pinfunction "2_2") (pintype "passive"))
      (node (ref "S2") (pin "5") (pinfunction "5_5") (pintype "passive"))
      (node (ref "U4") (pin "14") (pinfunction "A2_14") (pintype "passive"))
      (node (ref "U5") (pin "8") (pinfunction "A6_8") (pintype "passive"))
    )
    (net (code "9") (name "/A7") (class "Default")
      (node (ref "R1") (pin "1") (pinfunction "1_1") (pintype "passive"))
      (node (ref "S1") (pin "2") (pinfunction "2_2") (pintype "passive"))
      (node (ref "S1") (pin "5") (pinfunction "5_5") (pintype "passive"))
      (node (ref "U4") (pin "12") (pinfunction "A3_12") (pintype "passive"))
      (node (ref "U5") (pin "9") (pinfunction "A7_9") (pintype "passive"))
    )
    (net (code "10") (name "/B0") (class "Default")
      (node (ref "R16") (pin "1") (pinfunction "1_1") (pintype "passive"))
      (node (ref "S16") (pin "2") (pinfunction "2_2") (pintype "passive"))
      (node (ref "S16") (pin "5") (pinfunction "5_5") (pintype "passive"))
      (node (ref "U6") (pin "2") (pinfunction "A0_2") (pintype "passive"))
      (node (ref "U9") (pin "1") (pinfunction "A_1") (pintype "passive"))
    )
    (net (code "11") (name "/B1") (class "Default")
      (node (ref "R15") (pin "1") (pinfunction "1_1") (pintype "passive"))
      (node (ref "S15") (pin "2") (pinfunction "2_2") (pintype "passive"))
      (node (ref "S15") (pin "5") (pinfunction "5_5") (pintype "passive"))
      (node (ref "U6") (pin "3") (pinfunction "A1_3") (pintype "passive"))
      (node (ref "U9") (pin "5") (pinfunction "C_5") (pintype "passive"))
    )
    (net (code "12") (name "/B2") (class "Default")
      (node (ref "R14") (pin "1") (pinfunction "1_1") (pintype "passive"))
      (node (ref "S14") (pin "2") (pinfunction "2_2") (pintype "passive"))
      (node (ref "S14") (pin "5") (pinfunction "5_5") (pintype "passive"))
      (node (ref "U6") (pin "4") (pinfunction "A2_4") (pintype "passive"))
      (node (ref "U9") (pin "8") (pinfunction "E_8") (pintype "passive"))
    )
    (net (code "13") (name "/B3") (class "Default")
      (node (ref "R13") (pin "1") (pinfunction "1_1") (pintype "passive"))
      (node (ref "S13") (pin "2") (pinfunction "2_2") (pintype "passive"))
      (node (ref "S13") (pin "5") (pinfunction "5_5") (pintype "passive"))
      (node (ref "U6") (pin "5") (pinfunction "A3_5") (pintype "passive"))
      (node (ref "U9") (pin "12") (pinfunction "G_12") (pintype "passive"))
    )
    (net (code "14") (name "/B4") (class "Default")
      (node (ref "R12") (pin "1") (pinfunction "1_1") (pintype "passive"))
      (node (ref "S12") (pin "2") (pinfunction "2_2") (pintype "passive"))
      (node (ref "S12") (pin "5") (pinfunction "5_5") (pintype "passive"))
      (node (ref "U10") (pin "1") (pinfunction "A_1") (pintype "passive"))
      (node (ref "U6") (pin "6") (pinfunction "A4_6") (pintype "passive"))
    )
    (net (code "15") (name "/B5") (class "Default")
      (node (ref "R11") (pin "1") (pinfunction "1_1") (pintype "passive"))
      (node (ref "S11") (pin "2") (pinfunction "2_2") (pintype "passive"))
      (node (ref "S11") (pin "5") (pinfunction "5_5") (pintype "passive"))
      (node (ref "U10") (pin "5") (pinfunction "C_5") (pintype "passive"))
      (node (ref "U6") (pin "7") (pinfunction "A5_7") (pintype "passive"))
    )
    (net (code "16") (name "/B6") (class "Default")
      (node (ref "R10") (pin "1") (pinfunction "1_1") (pintype "passive"))
      (node (ref "S10") (pin "2") (pinfunction "2_2") (pintype "passive"))
      (node (ref "S10") (pin "5") (pinfunction "5_5") (pintype "passive"))
      (node (ref "U10") (pin "8") (pinfunction "E_8") (pintype "passive"))
      (node (ref "U6") (pin "8") (pinfunction "A6_8") (pintype "passive"))
    )
    (net (code "17") (name "/B7") (class "Default")
      (node (ref "R9") (pin "1") (pinfunction "1_1") (pintype "passive"))
      (node (ref "S9") (pin "2") (pinfunction "2_2") (pintype "passive"))
      (node (ref "S9") (pin "5") (pinfunction "5_5") (pintype "passive"))
      (node (ref "U10") (pin "12") (pinfunction "G_12") (pintype "passive"))
      (node (ref "U6") (pin "9") (pinfunction "A7_9") (pintype "passive"))
    )
    (net (code "18") (name "/DIGIT_1") (class "Default")
      (node (ref "DS1") (pin "3") (pinfunction "DIGIT_3") (pintype "passive"))
      (node (ref "DS1") (pin "8") (pinfunction "DIGIT_8") (pintype "passive"))
      (node (ref "Q1") (pin "2") (pinfunction "S_2") (pintype "passive"))
    )
    (net (code "19") (name "/DIGIT_2") (class "Default")
      (node (ref "DS2") (pin "3") (pinfunction "DIGIT_3") (pintype "passive"))
      (node (ref "DS2") (pin "8") (pinfunction "DIGIT_8") (pintype "passive"))
      (node (ref "Q2") (pin "2") (pinfunction "S_2") (pintype "passive"))
    )
    (net (code "20") (name "/DIGIT_3") (class "Default")
      (node (ref "DS3") (pin "3") (pinfunction "DIGIT_3") (pintype "passive"))
      (node (ref "DS3") (pin "8") (pinfunction "DIGIT_8") (pintype "passive"))
      (node (ref "Q3") (pin "2") (pinfunction "S_2") (pintype "passive"))
    )
    (net (code "21") (name "/DQ1") (class "Default")
      (node (ref "Q1") (pin "1") (pinfunction "G_1") (pintype "passive"))
      (node (ref "R36") (pin "2") (pinfunction "2_2") (pintype "passive"))
      (node (ref "U1") (pin "2") (pinfunction "PB0_2") (pintype "passive"))
    )
    (net (code "22") (name "/DQ2") (class "Default")
      (node (ref "Q2") (pin "1") (pinfunction "G_1") (pintype "passive"))
      (node (ref "R37") (pin "2") (pinfunction "2_2") (pintype "passive"))
      (node (ref "U1") (pin "3") (pinfunction "PB1_3") (pintype "passive"))
    )
    (net (code "23") (name "/DQ3") (class "Default")
      (node (ref "Q3") (pin "1") (pinfunction "G_1") (pintype "passive"))
      (node (ref "R38") (pin "2") (pinfunction "2_2") (pintype "passive"))
      (node (ref "U1") (pin "5") (pinfunction "PB2_5") (pintype "passive"))
    )
    (net (code "24") (name "/DS_A") (class "Default")
      (node (ref "R26") (pin "1") (pinfunction "1_1") (pintype "passive"))
      (node (ref "U2") (pin "13") (pinfunction "a_13") (pintype "passive"))
    )
    (net (code "25") (name "/DS_A_R") (class "Default")
      (node (ref "DS1") (pin "7") (pinfunction "a_7") (pintype "passive"))
      (node (ref "DS2") (pin "7") (pinfunction "a_7") (pintype "passive"))
      (node (ref "DS3") (pin "7") (pinfunction "a_7") (pintype "passive"))
      (node (ref "R26") (pin "2") (pinfunction "2_2") (pintype "passive"))
    )
    (net (code "26") (name "/DS_B") (class "Default")
      (node (ref "R27") (pin "1") (pinfunction "1_1") (pintype "passive"))
      (node (ref "U2") (pin "12") (pinfunction "b_12") (pintype "passive"))
    )
    (net (code "27") (name "/DS_B_R") (class "Default")
      (node (ref "DS1") (pin "6") (pinfunction "b_6") (pintype "passive"))
      (node (ref "DS2") (pin "6") (pinfunction "b_6") (pintype "passive"))
      (node (ref "DS3") (pin "6") (pinfunction "b_6") (pintype "passive"))
      (node (ref "R27") (pin "2") (pinfunction "2_2") (pintype "passive"))
    )
    (net (code "28") (name "/DS_C") (class "Default")
      (node (ref "R28") (pin "1") (pinfunction "1_1") (pintype "passive"))
      (node (ref "U2") (pin "11") (pinfunction "c_11") (pintype "passive"))
    )
    (net (code "29") (name "/DS_C_R") (class "Default")
      (node (ref "DS1") (pin "4") (pinfunction "c_4") (pintype "passive"))
      (node (ref "DS2") (pin "4") (pinfunction "c_4") (pintype "passive"))
      (node (ref "DS3") (pin "4") (pinfunction "c_4") (pintype "passive"))
      (node (ref "R28") (pin "2") (pinfunction "2_2") (pintype "passive"))
    )
    (net (code "30") (name "/DS_D") (class "Default")
      (node (ref "R29") (pin "1") (pinfunction "1_1") (pintype "passive"))
      (node (ref "U2") (pin "10") (pinfunction "d_10") (pintype "passive"))
    )
    (net (code "31") (name "/DS_D_R") (class "Default")
      (node (ref "DS1") (pin "2") (pinfunction "d_2") (pintype "passive"))
      (node (ref "DS2") (pin "2") (pinfunction "d_2") (pintype "passive"))
      (node (ref "DS3") (pin "2") (pinfunction "d_2") (pintype "passive"))
      (node (ref "R29") (pin "2") (pinfunction "2_2") (pintype "passive"))
    )
    (net (code "32") (name "/DS_E") (class "Default")
      (node (ref "R30") (pin "1") (pinfunction "1_1") (pintype "passive"))
      (node (ref "U2") (pin "9") (pinfunction "e_9") (pintype "passive"))
    )
    (net (code "33") (name "/DS_E_R") (class "Default")
      (node (ref "DS1") (pin "1") (pinfunction "e_1") (pintype "passive"))
      (node (ref "DS2") (pin "1") (pinfunction "e_1") (pintype "passive"))
      (node (ref "DS3") (pin "1") (pinfunction "e_1") (pintype "passive"))
      (node (ref "R30") (pin "2") (pinfunction "2_2") (pintype "passive"))
    )
    (net (code "34") (name "/DS_F") (class "Default")
      (node (ref "R31") (pin "1") (pinfunction "1_1") (pintype "passive"))
      (node (ref "U2") (pin "15") (pinfunction "f_15") (pintype "passive"))
    )
    (net (code "35") (name "/DS_F_R") (class "Default")
      (node (ref "DS1") (pin "9") (pinfunction "f_9") (pintype "passive"))
      (node (ref "DS2") (pin "9") (pinfunction "f_9") (pintype "passive"))
      (node (ref "DS3") (pin "9") (pinfunction "f_9") (pintype "passive"))
      (node (ref "R31") (pin "2") (pinfunction "2_2") (pintype "passive"))
    )
    (net (code "36") (name "/DS_G") (class "Default")
      (node (ref "R32") (pin "1") (pinfunction "1_1") (pintype "passive"))
      (node (ref "U2") (pin "14") (pinfunction "g_14") (pintype "passive"))
    )
    (net (code "37") (name "/DS_G_R") (class "Default")
      (node (ref "DS1") (pin "10") (pinfunction "g_10") (pintype "passive"))
      (node (ref "DS2") (pin "10") (pinfunction "g_10") (pintype "passive"))
      (node (ref "DS3") (pin "10") (pinfunction "g_10") (pintype "passive"))
      (node (ref "R32") (pin "2") (pinfunction "2_2") (pintype "passive"))
    )
    (net (code "38") (name "/IN_DS_A") (class "Default")
      (node (ref "U1") (pin "13") (pinfunction "PA0_13") (pintype "passive"))
      (node (ref "U2") (pin "7") (pinfunction "A_7") (pintype "passive"))
    )
    (net (code "39") (name "/IN_DS_B") (class "Default")
      (node (ref "U1") (pin "12") (pinfunction "PA1_12") (pintype "passive"))
      (node (ref "U2") (pin "1") (pinfunction "B_1") (pintype "passive"))
    )
    (net (code "40") (name "/IN_DS_C") (class "Default")
      (node (ref "U1") (pin "11") (pinfunction "PA2_11") (pintype "passive"))
      (node (ref "U2") (pin "2") (pinfunction "C_2") (pintype "passive"))
    )
    (net (code "41") (name "/IN_DS_D") (class "Default")
      (node (ref "U1") (pin "10") (pinfunction "PA3_10") (pintype "passive"))
      (node (ref "U2") (pin "6") (pinfunction "D_6") (pintype "passive"))
    )
    (net (code "42") (name "/K") (class "Default")
      (node (ref "S17") (pin "2") (pinfunction "2_2") (pintype "passive"))
      (node (ref "S17") (pin "5") (pinfunction "5_5") (pintype "passive"))
      (node (ref "U10") (pin "13") (pinfunction "H_13") (pintype "passive"))
      (node (ref "U10") (pin "2") (pinfunction "B_2") (pintype "passive"))
      (node (ref "U10") (pin "6") (pinfunction "D_6") (pintype "passive"))
      (node (ref "U10") (pin "9") (pinfunction "F_9") (pintype "passive"))
      (node (ref "U3") (pin "7") (pinfunction "CIN_7") (pintype "passive"))
      (node (ref "U9") (pin "13") (pinfunction "H_13") (pintype "passive"))
      (node (ref "U9") (pin "2") (pinfunction "B_2") (pintype "passive"))
      (node (ref "U9") (pin "6") (pinfunction "D_6") (pintype "passive"))
      (node (ref "U9") (pin "9") (pinfunction "F_9") (pintype "passive"))
    )
    (net (code "43") (name "/M0") (class "Default")
      (node (ref "U5") (pin "18") (pinfunction "B0_18") (pintype "passive"))
      (node (ref "U6") (pin "18") (pinfunction "B0_18") (pintype "passive"))
      (node (ref "U7") (pin "18") (pinfunction "B0_18") (pintype "passive"))
      (node (ref "U8") (pin "4") (pinfunction "D0_4") (pintype "passive"))
    )
    (net (code "44") (name "/M1") (class "Default")
      (node (ref "U5") (pin "17") (pinfunction "B1_17") (pintype "passive"))
      (node (ref "U6") (pin "17") (pinfunction "B1_17") (pintype "passive"))
      (node (ref "U7") (pin "17") (pinfunction "B1_17") (pintype "passive"))
      (node (ref "U8") (pin "3") (pinfunction "D1_3") (pintype "passive"))
    )
    (net (code "45") (name "/M2") (class "Default")
      (node (ref "U5") (pin "16") (pinfunction "B2_16") (pintype "passive"))
      (node (ref "U6") (pin "16") (pinfunction "B2_16") (pintype "passive"))
      (node (ref "U7") (pin "16") (pinfunction "B2_16") (pintype "passive"))
      (node (ref "U8") (pin "2") (pinfunction "D2_2") (pintype "passive"))
    )
    (net (code "46") (name "/M3") (class "Default")
      (node (ref "U5") (pin "15") (pinfunction "B3_15") (pintype "passive"))
      (node (ref "U6") (pin "15") (pinfunction "B3_15") (pintype "passive"))
      (node (ref "U7") (pin "15") (pinfunction "B3_15") (pintype "passive"))
      (node (ref "U8") (pin "1") (pinfunction "D3_1") (pintype "passive"))
    )
    (net (code "47") (name "/M4") (class "Default")
      (node (ref "U5") (pin "14") (pinfunction "B4_14") (pintype "passive"))
      (node (ref "U6") (pin "14") (pinfunction "B4_14") (pintype "passive"))
      (node (ref "U7") (pin "14") (pinfunction "B4_14") (pintype "passive"))
      (node (ref "U8") (pin "15") (pinfunction "D4_15") (pintype "passive"))
    )
    (net (code "48") (name "/M5") (class "Default")
      (node (ref "U5") (pin "13") (pinfunction "B5_13") (pintype "passive"))
      (node (ref "U6") (pin "13") (pinfunction "B5_13") (pintype "passive"))
      (node (ref "U7") (pin "13") (pinfunction "B5_13") (pintype "passive"))
      (node (ref "U8") (pin "14") (pinfunction "D5_14") (pintype "passive"))
    )
    (net (code "49") (name "/M6") (class "Default")
      (node (ref "U5") (pin "12") (pinfunction "B6_12") (pintype "passive"))
      (node (ref "U6") (pin "12") (pinfunction "B6_12") (pintype "passive"))
      (node (ref "U7") (pin "12") (pinfunction "B6_12") (pintype "passive"))
      (node (ref "U8") (pin "13") (pinfunction "D6_13") (pintype "passive"))
    )
    (net (code "50") (name "/M7") (class "Default")
      (node (ref "U5") (pin "11") (pinfunction "B7_11") (pintype "passive"))
      (node (ref "U6") (pin "11") (pinfunction "B7_11") (pintype "passive"))
      (node (ref "U7") (pin "11") (pinfunction "B7_11") (pintype "passive"))
      (node (ref "U8") (pin "12") (pinfunction "D7_12") (pintype "passive"))
    )
    (net (code "51") (name "/M_A") (class "Default")
      (node (ref "J2") (pin "6") (pinfunction "6_6") (pintype "passive"))
      (node (ref "U1") (pin "9") (pinfunction "PA4_9") (pintype "passive"))
      (node (ref "U8") (pin "11") (pinfunction "A_11") (pintype "passive"))
    )
    (net (code "52") (name "/M_B") (class "Default")
      (node (ref "J2") (pin "5") (pinfunction "5_5") (pintype "passive"))
      (node (ref "U1") (pin "8") (pinfunction "PA5_8") (pintype "passive"))
      (node (ref "U8") (pin "10") (pinfunction "B_10") (pintype "passive"))
    )
    (net (code "53") (name "/M_C") (class "Default")
      (node (ref "J2") (pin "4") (pinfunction "4_4") (pintype "passive"))
      (node (ref "U1") (pin "7") (pinfunction "PA6_7") (pintype "passive"))
      (node (ref "U8") (pin "9") (pinfunction "C_9") (pintype "passive"))
    )
    (net (code "54") (name "/M_Y") (class "Default")
      (node (ref "U1") (pin "6") (pinfunction "PA7_6") (pintype "passive"))
      (node (ref "U8") (pin "5") (pinfunction "Y_5") (pintype "passive"))
    )
    (net (code "55") (name "/OE_A") (class "Default")
      (node (ref "R33") (pin "2") (pinfunction "2_2") (pintype "passive"))
      (node (ref "S18") (pin "1") (pinfunction "1_1") (pintype "passive"))
      (node (ref "S18") (pin "5") (pinfunction "4_5") (pintype "passive"))
      (node (ref "U5") (pin "19") (pinfunction "OE_19") (pintype "passive"))
    )
    (net (code "56") (name "/OE_B") (class "Default")
      (node (ref "R34") (pin "2") (pinfunction "2_2") (pintype "passive"))
      (node (ref "S18") (pin "2") (pinfunction "2_2") (pintype "passive"))
      (node (ref "S18") (pin "6") (pinfunction "5_6") (pintype "passive"))
      (node (ref "U6") (pin "19") (pinfunction "OE_19") (pintype "passive"))
    )
    (net (code "57") (name "/OE_S") (class "Default")
      (node (ref "R35") (pin "2") (pinfunction "2_2") (pintype "passive"))
      (node (ref "S18") (pin "4") (pinfunction "4_4") (pintype "passive"))
      (node (ref "S18") (pin "8") (pinfunction "8_8") (pintype "passive"))
      (node (ref "U7") (pin "19") (pinfunction "OE_19") (pintype "passive"))
    )
    (net (code "58") (name "/RESET") (class "Default")
      (node (ref "J2") (pin "3") (pinfunction "3_3") (pintype "passive"))
      (node (ref "U1") (pin "4") (pinfunction "PB3_4") (pintype "passive"))
    )
    (net (code "59") (name "/S0") (class "Default")
      (node (ref "R25") (pin "1") (pinfunction "1_1") (pintype "passive"))
      (node (ref "U3") (pin "4") (pinfunction "S0_4") (pintype "passive"))
      (node (ref "U7") (pin "2") (pinfunction "A0_2") (pintype "passive"))
    )
    (net (code "60") (name "/S1") (class "Default")
      (node (ref "R24") (pin "1") (pinfunction "1_1") (pintype "passive"))
      (node (ref "U3") (pin "1") (pinfunction "S1_1") (pintype "passive"))
      (node (ref "U7") (pin "3") (pinfunction "A1_3") (pintype "passive"))
    )
    (net (code "61") (name "/S2") (class "Default")
      (node (ref "R23") (pin "1") (pinfunction "1_1") (pintype "passive"))
      (node (ref "U3") (pin "13") (pinfunction "S2_13") (pintype "passive"))
      (node (ref "U7") (pin "4") (pinfunction "A2_4") (pintype "passive"))
    )
    (net (code "62") (name "/S3") (class "Default")
      (node (ref "R22") (pin "1") (pinfunction "1_1") (pintype "passive"))
      (node (ref "U3") (pin "10") (pinfunction "S3_10") (pintype "passive"))
      (node (ref "U7") (pin "5") (pinfunction "A3_5") (pintype "passive"))
    )
    (net (code "63") (name "/S4") (class "Default")
      (node (ref "R21") (pin "1") (pinfunction "1_1") (pintype "passive"))
      (node (ref "U4") (pin "4") (pinfunction "S0_4") (pintype "passive"))
      (node (ref "U7") (pin "6") (pinfunction "A4_6") (pintype "passive"))
    )
    (net (code "64") (name "/S5") (class "Default")
      (node (ref "R20") (pin "1") (pinfunction "1_1") (pintype "passive"))
      (node (ref "U4") (pin "1") (pinfunction "S1_1") (pintype "passive"))
      (node (ref "U7") (pin "7") (pinfunction "A5_7") (pintype "passive"))
    )
    (net (code "65") (name "/S6") (class "Default")
      (node (ref "R19") (pin "1") (pinfunction "1_1") (pintype "passive"))
      (node (ref "U4") (pin "13") (pinfunction "S2_13") (pintype "passive"))
      (node (ref "U7") (pin "8") (pinfunction "A6_8") (pintype "passive"))
    )
    (net (code "66") (name "/S7") (class "Default")
      (node (ref "R18") (pin "1") (pinfunction "1_1") (pintype "passive"))
      (node (ref "U4") (pin "10") (pinfunction "S3_10") (pintype "passive"))
      (node (ref "U7") (pin "9") (pinfunction "A7_9") (pintype "passive"))
    )
    (net (code "67") (name "/S8") (class "Default")
      (node (ref "R17") (pin "1") (pinfunction "1_1") (pintype "passive"))
      (node (ref "U4") (pin "9") (pinfunction "COUT_9") (pintype "passive"))
    )
    (net (code "68") (name "/VCC") (class "Default")
      (node (ref "C1") (pin "2") (pinfunction "2_2") (pintype "passive"))
      (node (ref "J1") (pin "A9") (pinfunction "VBUS_A9") (pintype "passive"))
      (node (ref "J1") (pin "B9") (pinfunction "VBUS_B9") (pintype "passive"))
      (node (ref "VCC") (pin "1") (pinfunction "1_1") (pintype "passive"))
      (node (ref "VR1") (pin "3") (pinfunction "IN_3") (pintype "passive"))
    )
    (net (code "69") (name "/XB0") (class "Default")
      (node (ref "U3") (pin "6") (pinfunction "B0_6") (pintype "passive"))
      (node (ref "U9") (pin "3") (pinfunction "J_3") (pintype "passive"))
    )
    (net (code "70") (name "/XB1") (class "Default")
      (node (ref "U3") (pin "2") (pinfunction "B1_2") (pintype "passive"))
      (node (ref "U9") (pin "4") (pinfunction "K_4") (pintype "passive"))
    )
    (net (code "71") (name "/XB2") (class "Default")
      (node (ref "U3") (pin "15") (pinfunction "B2_15") (pintype "passive"))
      (node (ref "U9") (pin "10") (pinfunction "L_10") (pintype "passive"))
    )
    (net (code "72") (name "/XB3") (class "Default")
      (node (ref "U3") (pin "11") (pinfunction "B3_11") (pintype "passive"))
      (node (ref "U9") (pin "11") (pinfunction "M_11") (pintype "passive"))
    )
    (net (code "73") (name "/XB4") (class "Default")
      (node (ref "U10") (pin "3") (pinfunction "J_3") (pintype "passive"))
      (node (ref "U4") (pin "6") (pinfunction "B0_6") (pintype "passive"))
    )
    (net (code "74") (name "/XB5") (class "Default")
      (node (ref "U10") (pin "4") (pinfunction "K_4") (pintype "passive"))
      (node (ref "U4") (pin "2") (pinfunction "B1_2") (pintype "passive"))
    )
    (net (code "75") (name "/XB6") (class "Default")
      (node (ref "U10") (pin "10") (pinfunction "L_10") (pintype "passive"))
      (node (ref "U4") (pin "15") (pinfunction "B2_15") (pintype "passive"))
    )
    (net (code "76") (name "/XB7") (class "Default")
      (node (ref "U10") (pin "11") (pinfunction "M_11") (pintype "passive"))
      (node (ref "U4") (pin "11") (pinfunction "B3_11") (pintype "passive"))
    )
    (net (code "77") (name "GND") (class "Default")
      (node (ref "C1") (pin "1") (pinfunction "1_1") (pintype "passive"))
      (node (ref "C2") (pin "1") (pinfunction "1_1") (pintype "passive"))
      (node (ref "C3") (pin "1") (pinfunction "1_1") (pintype "passive"))
      (node (ref "C4") (pin "1") (pinfunction "1_1") (pintype "passive"))
      (node (ref "C5") (pin "1") (pinfunction "1_1") (pintype "passive"))
      (node (ref "D1") (pin "2") (pinfunction "2_2") (pintype "passive"))
      (node (ref "D10") (pin "2") (pinfunction "2_2") (pintype "passive"))
      (node (ref "D11") (pin "2") (pinfunction "2_2") (pintype "passive"))
      (node (ref "D12") (pin "2") (pinfunction "2_2") (pintype "passive"))
      (node (ref "D13") (pin "2") (pinfunction "2_2") (pintype "passive"))
      (node (ref "D14") (pin "2") (pinfunction "2_2") (pintype "passive"))
      (node (ref "D15") (pin "2") (pinfunction "2_2") (pintype "passive"))
      (node (ref "D16") (pin "2") (pinfunction "2_2") (pintype "passive"))
      (node (ref "D17") (pin "2") (pinfunction "2_2") (pintype "passive"))
      (node (ref "D18") (pin "2") (pinfunction "2_2") (pintype "passive"))
      (node (ref "D19") (pin "2") (pinfunction "2_2") (pintype "passive"))
      (node (ref "D2") (pin "2") (pinfunction "2_2") (pintype "passive"))
      (node (ref "D20") (pin "2") (pinfunction "2_2") (pintype "passive"))
      (node (ref "D21") (pin "2") (pinfunction "2_2") (pintype "passive"))
      (node (ref "D22") (pin "2") (pinfunction "2_2") (pintype "passive"))
      (node (ref "D23") (pin "2") (pinfunction "2_2") (pintype "passive"))
      (node (ref "D24") (pin "2") (pinfunction "2_2") (pintype "passive"))
      (node (ref "D25") (pin "2") (pinfunction "2_2") (pintype "passive"))
      (node (ref "D3") (pin "2") (pinfunction "2_2") (pintype "passive"))
      (node (ref "D4") (pin "2") (pinfunction "2_2") (pintype "passive"))
      (node (ref "D5") (pin "2") (pinfunction "2_2") (pintype "passive"))
      (node (ref "D6") (pin "2") (pinfunction "2_2") (pintype "passive"))
      (node (ref "D7") (pin "2") (pinfunction "2_2") (pintype "passive"))
      (node (ref "D8") (pin "2") (pinfunction "2_2") (pintype "passive"))
      (node (ref "D9") (pin "2") (pinfunction "2_2") (pintype "passive"))
      (node (ref "GND") (pin "1") (pinfunction "1_1") (pintype "passive"))
      (node (ref "J1") (pin "A12") (pinfunction "GND_A12") (pintype "passive"))
      (node (ref "J1") (pin "B12") (pinfunction "GND_B12") (pintype "passive"))
      (node (ref "J2") (pin "1") (pinfunction "1_1") (pintype "passive"))
      (node (ref "R36") (pin "1") (pinfunction "1_1") (pintype "passive"))
      (node (ref "R37") (pin "1") (pinfunction "1_1") (pintype "passive"))
      (node (ref "R38") (pin "1") (pinfunction "1_1") (pintype "passive"))
      (node (ref "RCC1") (pin "2") (pinfunction "2_2") (pintype "passive"))
      (node (ref "RCC2") (pin "2") (pinfunction "2_2") (pintype "passive"))
      (node (ref "S1") (pin "3") (pinfunction "3_3") (pintype "passive"))
      (node (ref "S1") (pin "6") (pinfunction "6_6") (pintype "passive"))
      (node (ref "S10") (pin "3") (pinfunction "3_3") (pintype "passive"))
      (node (ref "S10") (pin "6") (pinfunction "6_6") (pintype "passive"))
      (node (ref "S11") (pin "3") (pinfunction "3_3") (pintype "passive"))
      (node (ref "S11") (pin "6") (pinfunction "6_6") (pintype "passive"))
      (node (ref "S12") (pin "3") (pinfunction "3_3") (pintype "passive"))
      (node (ref "S12") (pin "6") (pinfunction "6_6") (pintype "passive"))
      (node (ref "S13") (pin "3") (pinfunction "3_3") (pintype "passive"))
      (node (ref "S13") (pin "6") (pinfunction "6_6") (pintype "passive"))
      (node (ref "S14") (pin "3") (pinfunction "3_3") (pintype "passive"))
      (node (ref "S14") (pin "6") (pinfunction "6_6") (pintype "passive"))
      (node (ref "S15") (pin "3") (pinfunction "3_3") (pintype "passive"))
      (node (ref "S15") (pin "6") (pinfunction "6_6") (pintype "passive"))
      (node (ref "S16") (pin "3") (pinfunction "3_3") (pintype "passive"))
      (node (ref "S16") (pin "6") (pinfunction "6_6") (pintype "passive"))
      (node (ref "S17") (pin "1") (pinfunction "1_1") (pintype "passive"))
      (node (ref "S17") (pin "4") (pinfunction "4_4") (pintype "passive"))
      (node (ref "S18") (pin "3") (pinfunction "3_3") (pintype "passive"))
      (node (ref "S18") (pin "7") (pinfunction "7_7") (pintype "passive"))
      (node (ref "S2") (pin "3") (pinfunction "3_3") (pintype "passive"))
      (node (ref "S2") (pin "6") (pinfunction "6_6") (pintype "passive"))
      (node (ref "S3") (pin "3") (pinfunction "3_3") (pintype "passive"))
      (node (ref "S3") (pin "6") (pinfunction "6_6") (pintype "passive"))
      (node (ref "S4") (pin "3") (pinfunction "3_3") (pintype "passive"))
      (node (ref "S4") (pin "6") (pinfunction "6_6") (pintype "passive"))
      (node (ref "S5") (pin "3") (pinfunction "3_3") (pintype "passive"))
      (node (ref "S5") (pin "6") (pinfunction "6_6") (pintype "passive"))
      (node (ref "S6") (pin "3") (pinfunction "3_3") (pintype "passive"))
      (node (ref "S6") (pin "6") (pinfunction "6_6") (pintype "passive"))
      (node (ref "S7") (pin "3") (pinfunction "3_3") (pintype "passive"))
      (node (ref "S7") (pin "6") (pinfunction "6_6") (pintype "passive"))
      (node (ref "S8") (pin "3") (pinfunction "3_3") (pintype "passive"))
      (node (ref "S8") (pin "6") (pinfunction "6_6") (pintype "passive"))
      (node (ref "S9") (pin "3") (pinfunction "3_3") (pintype "passive"))
      (node (ref "S9") (pin "6") (pinfunction "6_6") (pintype "passive"))
      (node (ref "U1") (pin "14") (pinfunction "GND_14") (pintype "passive"))
      (node (ref "U10") (pin "7") (pinfunction "VSS_7") (pintype "passive"))
      (node (ref "U2") (pin "5") (pinfunction "LE_5") (pintype "passive"))
      (node (ref "U2") (pin "8") (pinfunction "VSS_8") (pintype "passive"))
      (node (ref "U3") (pin "8") (pinfunction "GND_8") (pintype "passive"))
      (node (ref "U4") (pin "8") (pinfunction "GND_8") (pintype "passive"))
      (node (ref "U5") (pin "10") (pinfunction "GND_10") (pintype "passive"))
      (node (ref "U6") (pin "10") (pinfunction "GND_10") (pintype "passive"))
      (node (ref "U7") (pin "10") (pinfunction "GND_10") (pintype "passive"))
      (node (ref "U8") (pin "7") (pinfunction "EN_7") (pintype "passive"))
      (node (ref "U8") (pin "8") (pinfunction "GND_8") (pintype "passive"))
      (node (ref "U9") (pin "7") (pinfunction "VSS_7") (pintype "passive"))
      (node (ref "VR1") (pin "1") (pinfunction "GND_1") (pintype "passive"))
    )
    (net (code "78") (name "Net-(D1-Pad1)") (class "Default")
      (node (ref "D1") (pin "1") (pinfunction "1_1") (pintype "passive"))
      (node (ref "R1") (pin "2") (pinfunction "2_2") (pintype "passive"))
    )
    (net (code "79") (name "Net-(D2-Pad1)") (class "Default")
      (node (ref "D2") (pin "1") (pinfunction "1_1") (pintype "passive"))
      (node (ref "R2") (pin "2") (pinfunction "2_2") (pintype "passive"))
    )
    (net (code "80") (name "Net-(D3-Pad1)") (class "Default")
      (node (ref "D3") (pin "1") (pinfunction "1_1") (pintype "passive"))
      (node (ref "R3") (pin "2") (pinfunction "2_2") (pintype "passive"))
    )
    (net (code "81") (name "Net-(D4-Pad1)") (class "Default")
      (node (ref "D4") (pin "1") (pinfunction "1_1") (pintype "passive"))
      (node (ref "R4") (pin "2") (pinfunction "2_2") (pintype "passive"))
    )
    (net (code "82") (name "Net-(D5-Pad1)") (class "Default")
      (node (ref "D5") (pin "1") (pinfunction "1_1") (pintype "passive"))
      (node (ref "R5") (pin "2") (pinfunction "2_2") (pintype "passive"))
    )
    (net (code "83") (name "Net-(D6-Pad1)") (class "Default")
      (node (ref "D6") (pin "1") (pinfunction "1_1") (pintype "passive"))
      (node (ref "R6") (pin "2") (pinfunction "2_2") (pintype "passive"))
    )
    (net (code "84") (name "Net-(D7-Pad1)") (class "Default")
      (node (ref "D7") (pin "1") (pinfunction "1_1") (pintype "passive"))
      (node (ref "R7") (pin "2") (pinfunction "2_2") (pintype "passive"))
    )
    (net (code "85") (name "Net-(D8-Pad1)") (class "Default")
      (node (ref "D8") (pin "1") (pinfunction "1_1") (pintype "passive"))
      (node (ref "R8") (pin "2") (pinfunction "2_2") (pintype "passive"))
    )
    (net (code "86") (name "Net-(D9-Pad1)") (class "Default")
      (node (ref "D9") (pin "1") (pinfunction "1_1") (pintype "passive"))
      (node (ref "R9") (pin "2") (pinfunction "2_2") (pintype "passive"))
    )
    (net (code "87") (name "Net-(D10-Pad1)") (class "Default")
      (node (ref "D10") (pin "1") (pinfunction "1_1") (pintype "passive"))
      (node (ref "R10") (pin "2") (pinfunction "2_2") (pintype "passive"))
    )
    (net (code "88") (name "Net-(D11-Pad1)") (class "Default")
      (node (ref "D11") (pin "1") (pinfunction "1_1") (pintype "passive"))
      (node (ref "R11") (pin "2") (pinfunction "2_2") (pintype "passive"))
    )
    (net (code "89") (name "Net-(D12-Pad1)") (class "Default")
      (node (ref "D12") (pin "1") (pinfunction "1_1") (pintype "passive"))
      (node (ref "R12") (pin "2") (pinfunction "2_2") (pintype "passive"))
    )
    (net (code "90") (name "Net-(D13-Pad1)") (class "Default")
      (node (ref "D13") (pin "1") (pinfunction "1_1") (pintype "passive"))
      (node (ref "R13") (pin "2") (pinfunction "2_2") (pintype "passive"))
    )
    (net (code "91") (name "Net-(D14-Pad1)") (class "Default")
      (node (ref "D14") (pin "1") (pinfunction "1_1") (pintype "passive"))
      (node (ref "R14") (pin "2") (pinfunction "2_2") (pintype "passive"))
    )
    (net (code "92") (name "Net-(D15-Pad1)") (class "Default")
      (node (ref "D15") (pin "1") (pinfunction "1_1") (pintype "passive"))
      (node (ref "R15") (pin "2") (pinfunction "2_2") (pintype "passive"))
    )
    (net (code "93") (name "Net-(D16-Pad1)") (class "Default")
      (node (ref "D16") (pin "1") (pinfunction "1_1") (pintype "passive"))
      (node (ref "R16") (pin "2") (pinfunction "2_2") (pintype "passive"))
    )
    (net (code "94") (name "Net-(D17-Pad1)") (class "Default")
      (node (ref "D17") (pin "1") (pinfunction "1_1") (pintype "passive"))
      (node (ref "R17") (pin "2") (pinfunction "2_2") (pintype "passive"))
    )
    (net (code "95") (name "Net-(D18-Pad1)") (class "Default")
      (node (ref "D18") (pin "1") (pinfunction "1_1") (pintype "passive"))
      (node (ref "R18") (pin "2") (pinfunction "2_2") (pintype "passive"))
    )
    (net (code "96") (name "Net-(D19-Pad1)") (class "Default")
      (node (ref "D19") (pin "1") (pinfunction "1_1") (pintype "passive"))
      (node (ref "R19") (pin "2") (pinfunction "2_2") (pintype "passive"))
    )
    (net (code "97") (name "Net-(D20-Pad1)") (class "Default")
      (node (ref "D20") (pin "1") (pinfunction "1_1") (pintype "passive"))
      (node (ref "R20") (pin "2") (pinfunction "2_2") (pintype "passive"))
    )
    (net (code "98") (name "Net-(D21-Pad1)") (class "Default")
      (node (ref "D21") (pin "1") (pinfunction "1_1") (pintype "passive"))
      (node (ref "R21") (pin "2") (pinfunction "2_2") (pintype "passive"))
    )
    (net (code "99") (name "Net-(D22-Pad1)") (class "Default")
      (node (ref "D22") (pin "1") (pinfunction "1_1") (pintype "passive"))
      (node (ref "R22") (pin "2") (pinfunction "2_2") (pintype "passive"))
    )
    (net (code "100") (name "Net-(D23-Pad1)") (class "Default")
      (node (ref "D23") (pin "1") (pinfunction "1_1") (pintype "passive"))
      (node (ref "R23") (pin "2") (pinfunction "2_2") (pintype "passive"))
    )
    (net (code "101") (name "Net-(D24-Pad1)") (class "Default")
      (node (ref "D24") (pin "1") (pinfunction "1_1") (pintype "passive"))
      (node (ref "R24") (pin "2") (pinfunction "2_2") (pintype "passive"))
    )
    (net (code "102") (name "Net-(D25-Pad1)") (class "Default")
      (node (ref "D25") (pin "1") (pinfunction "1_1") (pintype "passive"))
      (node (ref "R25") (pin "2") (pinfunction "2_2") (pintype "passive"))
    )
    (net (code "103") (name "Net-(J1-CC1-PadA5)") (class "Default")
      (node (ref "J1") (pin "A5") (pinfunction "CC1_A5") (pintype "passive"))
      (node (ref "RCC2") (pin "1") (pinfunction "1_1") (pintype "passive"))
    )
    (net (code "104") (name "Net-(J1-CC1-PadB5)") (class "Default")
      (node (ref "J1") (pin "B5") (pinfunction "CC1_B5") (pintype "passive"))
      (node (ref "RCC1") (pin "1") (pinfunction "1_1") (pintype "passive"))
    )
    (net (code "105") (name "Net-(U3-COUT)") (class "Default")
      (node (ref "U3") (pin "9") (pinfunction "COUT_9") (pintype "passive"))
      (node (ref "U4") (pin "7") (pinfunction "CIN_7") (pintype "passive"))
    )
    (net (code "106") (name "unconnected-(DS1-DP-Pad5)") (class "Default")
      (node (ref "DS1") (pin "5") (pinfunction "DP_5") (pintype "passive+no_connect"))
    )
    (net (code "107") (name "unconnected-(DS2-DP-Pad5)") (class "Default")
      (node (ref "DS2") (pin "5") (pinfunction "DP_5") (pintype "passive+no_connect"))
    )
    (net (code "108") (name "unconnected-(DS3-DP-Pad5)") (class "Default")
      (node (ref "DS3") (pin "5") (pinfunction "DP_5") (pintype "passive+no_connect"))
    )
    (net (code "109") (name "unconnected-(U5-NC-Pad1)") (class "Default")
      (node (ref "U5") (pin "1") (pinfunction "NC_1") (pintype "passive+no_connect"))
    )
    (net (code "110") (name "unconnected-(U6-NC-Pad1)") (class "Default")
      (node (ref "U6") (pin "1") (pinfunction "NC_1") (pintype "passive+no_connect"))
    )
    (net (code "111") (name "unconnected-(U7-NC-Pad1)") (class "Default")
      (node (ref "U7") (pin "1") (pinfunction "NC_1") (pintype "passive+no_connect"))
    )
    (net (code "112") (name "unconnected-(U8-W-Pad6)") (class "Default")
      (node (ref "U8") (pin "6") (pinfunction "W_6") (pintype "passive+no_connect"))
    )
  )
)
